# LCCAtmegaXXM1.net
KiCad netlist of a schematic drawn in Altium Designer
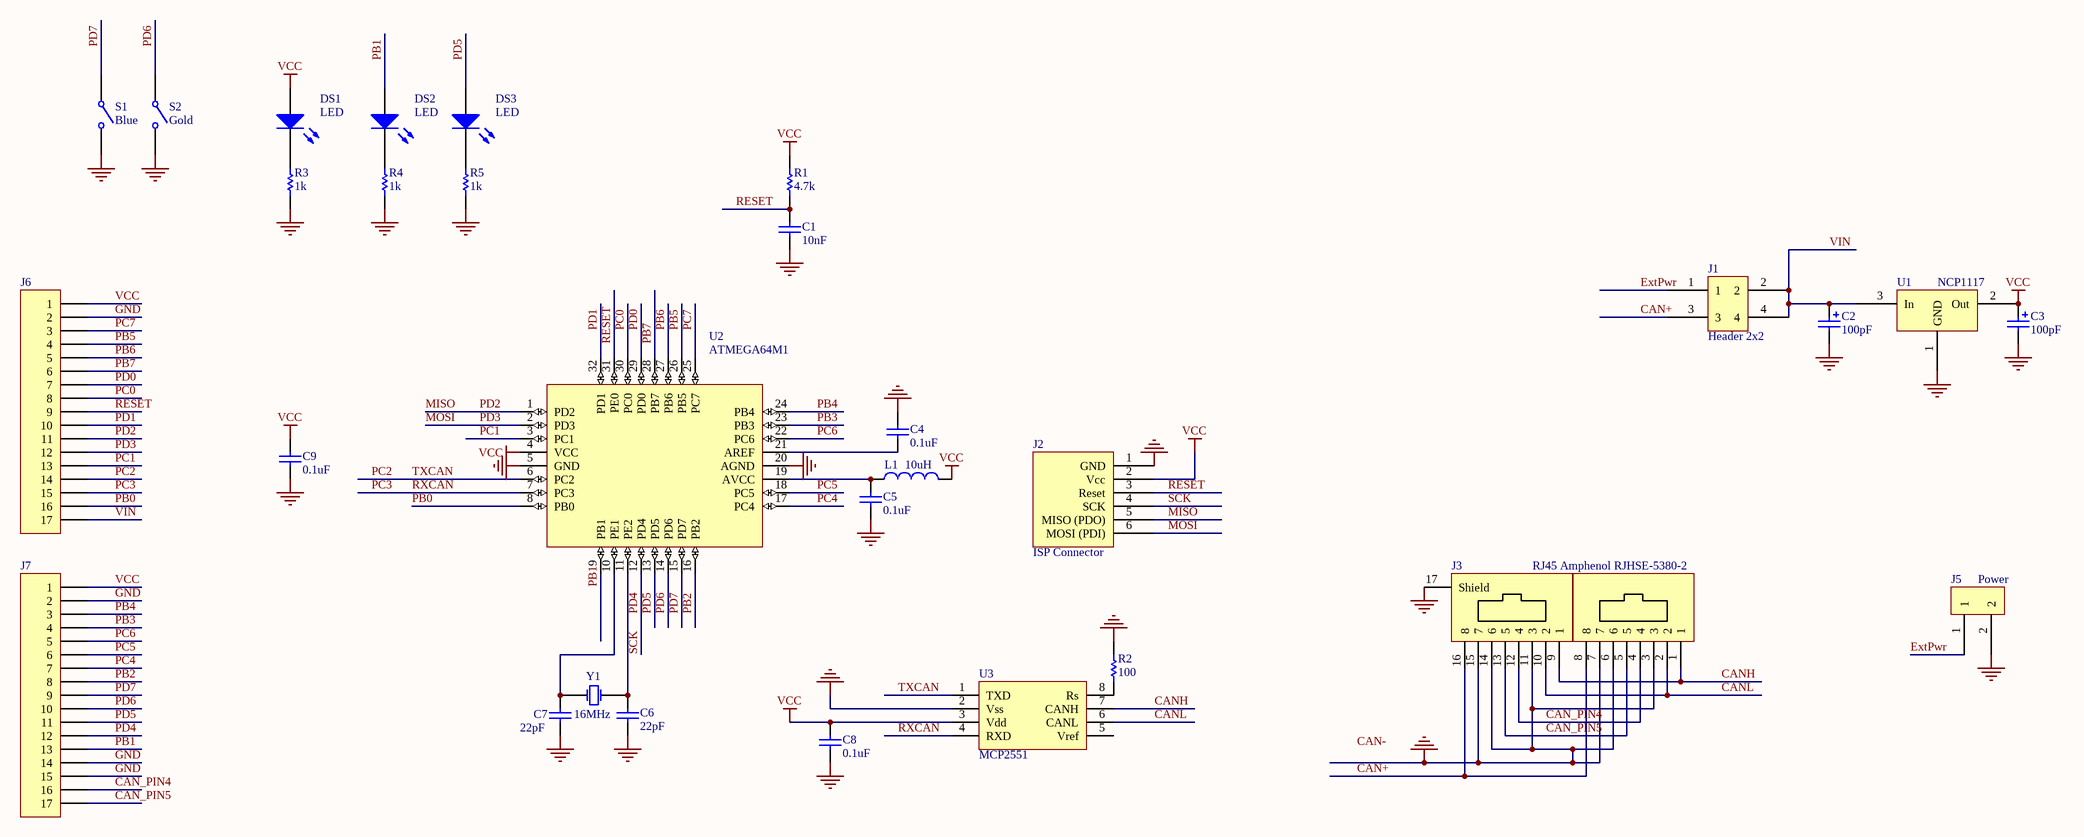
[diagram p0: LCCAtmegaXXM1.SchDoc]

(export (version "E")
  (design (tool "Eeschema 10.0.6"))
  (components
    (comp (ref "C1")
      (value "10nF")
      (footprint "Cap SMD 0805A")
      (description "Capacitor")
      (fields (field (name "Comment") "Cap") (field (name "PUBLISHER") "Altium Limited"))
      (libsource (lib "Custom") (part "Cap"))
    )
    (comp (ref "C2")
      (value "100pF")
      (footprint "Cap SMD Elect 5x5.3")
      (description "Polarized Capacitor (Radial)")
      (fields (field (name "Comment") "Cap Pol") (field (name "PUBLISHER") "Altium Limited"))
      (libsource (lib "Custom") (part "Cap Pol"))
    )
    (comp (ref "C3")
      (value "100pF")
      (footprint "Cap SMD Elect 5x5.3")
      (description "Polarized Capacitor (Radial)")
      (fields (field (name "Comment") "Cap Pol") (field (name "PUBLISHER") "Altium Limited"))
      (libsource (lib "Custom") (part "Cap Pol"))
    )
    (comp (ref "C4")
      (value "0.1uF")
      (footprint "Cap SMD 0805A")
      (description "Capacitor")
      (fields (field (name "Comment") "Cap") (field (name "PUBLISHER") "Altium Limited"))
      (libsource (lib "Custom") (part "Cap"))
    )
    (comp (ref "C5")
      (value "0.1uF")
      (footprint "Cap SMD 0805A")
      (description "Capacitor")
      (fields (field (name "Comment") "Cap") (field (name "PUBLISHER") "Altium Limited"))
      (libsource (lib "Custom") (part "Cap"))
    )
    (comp (ref "C6")
      (value "22pF")
      (footprint "Cap SMD 0805A")
      (description "Capacitor")
      (fields (field (name "Comment") "Cap") (field (name "PUBLISHER") "Altium Limited"))
      (libsource (lib "Custom") (part "Cap"))
    )
    (comp (ref "C7")
      (value "22pF")
      (footprint "Cap SMD 0805A")
      (description "Capacitor")
      (fields (field (name "Comment") "Cap") (field (name "PUBLISHER") "Altium Limited"))
      (libsource (lib "Custom") (part "Cap"))
    )
    (comp (ref "C8")
      (value "0.1uF")
      (footprint "Cap SMD 0805A")
      (description "Capacitor")
      (fields (field (name "Comment") "Cap") (field (name "PUBLISHER") "Altium Limited"))
      (libsource (lib "Custom") (part "Cap"))
    )
    (comp (ref "C9")
      (value "0.1uF")
      (footprint "Cap SMD 0805A")
      (description "Capacitor")
      (fields (field (name "Comment") "Cap") (field (name "PUBLISHER") "Altium Limited"))
      (libsource (lib "Custom") (part "Cap"))
    )
    (comp (ref "DS1")
      (value "LED")
      (footprint "LED SMD 0805")
      (description "RGB LED Common Anode")
      (fields (field (name "PUBLISHER") "Altium Limited"))
      (libsource (lib "Custom") (part "LED"))
    )
    (comp (ref "DS2")
      (value "LED")
      (footprint "LED SMD 0805")
      (description "RGB LED Common Anode")
      (fields (field (name "PUBLISHER") "Altium Limited"))
      (libsource (lib "Custom") (part "LED"))
    )
    (comp (ref "DS3")
      (value "LED")
      (footprint "LED SMD 0805")
      (description "RGB LED Common Anode")
      (fields (field (name "PUBLISHER") "Altium Limited"))
      (libsource (lib "Custom") (part "LED"))
    )
    (comp (ref "J1") (value "Header 2x2") (footprint "HDR2x2") (libsource (lib "Custom") (part "HDR2x2")))
    (comp (ref "J2")
      (value "ISP Connector")
      (footprint "PcbLib1:HDR2x3")
      (libsource (lib "Custom") (part "ISP Connector"))
    )
    (comp (ref "J3")
      (value "RJ45 Amphenol RJHSE-5380-2")
      (footprint "Amphenol RJHSE-5380-2")
      (libsource (lib "Custom") (part "RJ45-2"))
    )
    (comp (ref "J5")
      (value "Power")
      (footprint "DC 2.5mm PCB Jack")
      (libsource (lib "Custom") (part "SIP2 CONNECTOR"))
    )
    (comp (ref "J6")
      (value "Header 17")
      (footprint "HDR1X17")
      (description "Header, 17-Pin")
      (fields (field (name "PUBLISHER") "Altium Limited"))
      (libsource (lib "Miscellaneous Connectors") (part "Header 17"))
    )
    (comp (ref "J7")
      (value "Header 17")
      (footprint "HDR1X17")
      (description "Header, 17-Pin")
      (fields (field (name "PUBLISHER") "Altium Limited"))
      (libsource (lib "Miscellaneous Connectors") (part "Header 17"))
    )
    (comp (ref "L1")
      (value "10uH")
      (footprint "Cap SMD 0805A")
      (description "Inductor")
      (fields (field (name "PUBLISHER") "Altium Limited"))
      (libsource (lib "Miscellaneous Devices") (part "Inductor"))
    )
    (comp (ref "R1")
      (value "4.7k")
      (footprint "Res SMD 0805A")
      (fields (field (name "Comment") "Res1"))
      (libsource (lib "Custom") (part "Resistor"))
    )
    (comp (ref "R2")
      (value "100")
      (footprint "Res SMD 0805A")
      (fields (field (name "Comment") "Res1"))
      (libsource (lib "Custom") (part "Resistor"))
    )
    (comp (ref "R3")
      (value "1k")
      (footprint "Res SMD 0805A")
      (fields (field (name "Comment") "Res1"))
      (libsource (lib "Custom") (part "Resistor"))
    )
    (comp (ref "R4")
      (value "1k")
      (footprint "Res SMD 0805A")
      (fields (field (name "Comment") "Res1"))
      (libsource (lib "Custom") (part "Resistor"))
    )
    (comp (ref "R5")
      (value "1k")
      (footprint "Res SMD 0805A")
      (fields (field (name "Comment") "Res1"))
      (libsource (lib "Custom") (part "Resistor"))
    )
    (comp (ref "S1")
      (value "Blue")
      (footprint "SPST Tactile 6x3.5")
      (description "Push Button, Single-Pole, Single-Throw")
      (fields (field (name "PUBLISHER") "Altium Limited"))
      (libsource (lib "Custom") (part "SW-PB-SPST"))
    )
    (comp (ref "S2")
      (value "Gold")
      (footprint "SPST Tactile 6x3.5")
      (description "Push Button, Single-Pole, Single-Throw")
      (fields (field (name "PUBLISHER") "Altium Limited"))
      (libsource (lib "Custom") (part "SW-PB-SPST"))
    )
    (comp (ref "U1")
      (value "NCP1117")
      (footprint "SOT-223")
      (description "LDO Regulator")
      (libsource (lib "Custom") (part "NCP1117"))
    )
    (comp (ref "U2")
      (value "ATMEGA64M1")
      (footprint "TQFP32")
      (description "8-Bit AVR Microcontroller")
      (fields (field (name "PUBLISHER") "Altium Limited"))
      (libsource (lib "Custom") (part "ATMEGA64M1"))
    )
    (comp (ref "U3")
      (value "MCP2551")
      (footprint "SOIC8")
      (description "MCP2551 High Speed CAN Transceiver")
      (libsource (lib "Custom") (part "MCP2551"))
    )
    (comp (ref "Y1")
      (value "16MHz")
      (footprint "Crystal TXC SMD")
      (description "Crystal Oscillator")
      (fields (field (name "PUBLISHER") "Altium Limited"))
      (libsource (lib "Miscellaneous Devices") (part "XTAL"))
    )
  )
  (nets
    (net (code "1") (name "/CAN+") (class "Default")
      (node (ref "J1") (pin "3") (pinfunction "3_3") (pintype "passive"))
      (node (ref "J3") (pin "16") (pinfunction "8_16") (pintype "passive"))
      (node (ref "J3") (pin "8") (pinfunction "8_8") (pintype "passive"))
    )
    (net (code "3") (name "/CANH") (class "Default")
      (node (ref "J3") (pin "1") (pinfunction "1_1") (pintype "passive"))
      (node (ref "J3") (pin "9") (pinfunction "1_9") (pintype "passive"))
      (node (ref "U3") (pin "7") (pinfunction "CANH_7") (pintype "passive"))
    )
    (net (code "4") (name "/CANL") (class "Default")
      (node (ref "J3") (pin "10") (pinfunction "2_10") (pintype "passive"))
      (node (ref "J3") (pin "2") (pinfunction "2_2") (pintype "passive"))
      (node (ref "U3") (pin "6") (pinfunction "CANL_6") (pintype "passive"))
    )
    (net (code "5") (name "/CAN_PIN4") (class "Default")
      (node (ref "J3") (pin "12") (pinfunction "4_12") (pintype "passive"))
      (node (ref "J3") (pin "4") (pinfunction "4_4") (pintype "passive"))
      (node (ref "J7") (pin "16") (pinfunction "16_16") (pintype "passive"))
    )
    (net (code "6") (name "/CAN_PIN5") (class "Default")
      (node (ref "J3") (pin "13") (pinfunction "5_13") (pintype "passive"))
      (node (ref "J3") (pin "5") (pinfunction "5_5") (pintype "passive"))
      (node (ref "J7") (pin "17") (pinfunction "17_17") (pintype "passive"))
    )
    (net (code "7") (name "/ExtPwr") (class "Default")
      (node (ref "J1") (pin "1") (pinfunction "1_1") (pintype "passive"))
      (node (ref "J5") (pin "1") (pinfunction "1_1") (pintype "passive"))
    )
    (net (code "8") (name "/MISO") (class "Default")
      (node (ref "J2") (pin "5") (pinfunction "MISO_(PDO)_5") (pintype "passive"))
      (node (ref "J6") (pin "11") (pinfunction "11_11") (pintype "passive"))
      (node (ref "U2") (pin "1") (pinfunction "PD2_1") (pintype "bidirectional"))
    )
    (net (code "9") (name "/MOSI") (class "Default")
      (node (ref "J2") (pin "6") (pinfunction "MOSI_(PDI)_6") (pintype "passive"))
      (node (ref "J6") (pin "12") (pinfunction "12_12") (pintype "passive"))
      (node (ref "U2") (pin "2") (pinfunction "PD3_2") (pintype "bidirectional"))
    )
    (net (code "10") (name "/PB0") (class "Default")
      (node (ref "J6") (pin "16") (pinfunction "16_16") (pintype "passive"))
      (node (ref "U2") (pin "8") (pinfunction "PB0_8") (pintype "bidirectional"))
    )
    (net (code "11") (name "/PB1") (class "Default")
      (node (ref "DS2") (pin "A") (pinfunction "A_A") (pintype "passive"))
      (node (ref "J7") (pin "13") (pinfunction "13_13") (pintype "passive"))
      (node (ref "U2") (pin "9") (pinfunction "PB1_9") (pintype "bidirectional"))
    )
    (net (code "12") (name "/PB2") (class "Default")
      (node (ref "J7") (pin "8") (pinfunction "8_8") (pintype "passive"))
      (node (ref "U2") (pin "16") (pinfunction "PB2_16") (pintype "bidirectional"))
    )
    (net (code "13") (name "/PB3") (class "Default")
      (node (ref "J7") (pin "4") (pinfunction "4_4") (pintype "passive"))
      (node (ref "U2") (pin "23") (pinfunction "PB3_23") (pintype "bidirectional"))
    )
    (net (code "14") (name "/PB4") (class "Default")
      (node (ref "J7") (pin "3") (pinfunction "3_3") (pintype "passive"))
      (node (ref "U2") (pin "24") (pinfunction "PB4_24") (pintype "bidirectional"))
    )
    (net (code "15") (name "/PB5") (class "Default")
      (node (ref "J6") (pin "4") (pinfunction "4_4") (pintype "passive"))
      (node (ref "U2") (pin "26") (pinfunction "PB5_26") (pintype "bidirectional"))
    )
    (net (code "16") (name "/PB6") (class "Default")
      (node (ref "J6") (pin "5") (pinfunction "5_5") (pintype "passive"))
      (node (ref "U2") (pin "27") (pinfunction "PB6_27") (pintype "bidirectional"))
    )
    (net (code "17") (name "/PB7") (class "Default")
      (node (ref "J6") (pin "6") (pinfunction "6_6") (pintype "passive"))
      (node (ref "U2") (pin "28") (pinfunction "PB7_28") (pintype "bidirectional"))
    )
    (net (code "18") (name "/PC0") (class "Default")
      (node (ref "J6") (pin "8") (pinfunction "8_8") (pintype "passive"))
      (node (ref "U2") (pin "30") (pinfunction "PC0_30") (pintype "bidirectional"))
    )
    (net (code "19") (name "/PC1") (class "Default")
      (node (ref "J6") (pin "13") (pinfunction "13_13") (pintype "passive"))
      (node (ref "U2") (pin "3") (pinfunction "PC1_3") (pintype "bidirectional"))
    )
    (net (code "20") (name "/PC2") (class "Default")
      (node (ref "J6") (pin "14") (pinfunction "14_14") (pintype "passive"))
      (node (ref "U2") (pin "6") (pinfunction "PC2_6") (pintype "bidirectional"))
      (node (ref "U3") (pin "1") (pinfunction "TXD_1") (pintype "passive"))
    )
    (net (code "21") (name "/PC3") (class "Default")
      (node (ref "J6") (pin "15") (pinfunction "15_15") (pintype "passive"))
      (node (ref "U2") (pin "7") (pinfunction "PC3_7") (pintype "bidirectional"))
      (node (ref "U3") (pin "4") (pinfunction "RXD_4") (pintype "passive"))
    )
    (net (code "22") (name "/PC4") (class "Default")
      (node (ref "J7") (pin "7") (pinfunction "7_7") (pintype "passive"))
      (node (ref "U2") (pin "17") (pinfunction "PC4_17") (pintype "bidirectional"))
    )
    (net (code "23") (name "/PC5") (class "Default")
      (node (ref "J7") (pin "6") (pinfunction "6_6") (pintype "passive"))
      (node (ref "U2") (pin "18") (pinfunction "PC5_18") (pintype "bidirectional"))
    )
    (net (code "24") (name "/PC6") (class "Default")
      (node (ref "J7") (pin "5") (pinfunction "5_5") (pintype "passive"))
      (node (ref "U2") (pin "22") (pinfunction "PC6_22") (pintype "bidirectional"))
    )
    (net (code "25") (name "/PC7") (class "Default")
      (node (ref "J6") (pin "3") (pinfunction "3_3") (pintype "passive"))
      (node (ref "U2") (pin "25") (pinfunction "PC7_25") (pintype "bidirectional"))
    )
    (net (code "26") (name "/PD0") (class "Default")
      (node (ref "J6") (pin "7") (pinfunction "7_7") (pintype "passive"))
      (node (ref "U2") (pin "29") (pinfunction "PD0_29") (pintype "bidirectional"))
    )
    (net (code "27") (name "/PD1") (class "Default")
      (node (ref "J6") (pin "10") (pinfunction "10_10") (pintype "passive"))
      (node (ref "U2") (pin "32") (pinfunction "PD1_32") (pintype "bidirectional"))
    )
    (net (code "28") (name "/PD4") (class "Default")
      (node (ref "J2") (pin "4") (pinfunction "SCK_4") (pintype "passive"))
      (node (ref "J7") (pin "12") (pinfunction "12_12") (pintype "passive"))
      (node (ref "U2") (pin "12") (pinfunction "PD4_12") (pintype "bidirectional"))
    )
    (net (code "29") (name "/PD5") (class "Default")
      (node (ref "DS3") (pin "A") (pinfunction "A_A") (pintype "passive"))
      (node (ref "J7") (pin "11") (pinfunction "11_11") (pintype "passive"))
      (node (ref "U2") (pin "13") (pinfunction "PD5_13") (pintype "bidirectional"))
    )
    (net (code "30") (name "/PD6") (class "Default")
      (node (ref "J7") (pin "10") (pinfunction "10_10") (pintype "passive"))
      (node (ref "S2") (pin "1") (pinfunction "1_1") (pintype "passive"))
      (node (ref "U2") (pin "14") (pinfunction "PD6_14") (pintype "bidirectional"))
    )
    (net (code "31") (name "/PD7") (class "Default")
      (node (ref "J7") (pin "9") (pinfunction "9_9") (pintype "passive"))
      (node (ref "S1") (pin "1") (pinfunction "1_1") (pintype "passive"))
      (node (ref "U2") (pin "15") (pinfunction "PD7_15") (pintype "bidirectional"))
    )
    (net (code "32") (name "/RESET") (class "Default")
      (node (ref "C1") (pin "1") (pinfunction "1_1") (pintype "passive"))
      (node (ref "J2") (pin "3") (pinfunction "Reset_3") (pintype "passive"))
      (node (ref "J6") (pin "9") (pinfunction "9_9") (pintype "passive"))
      (node (ref "R1") (pin "1") (pinfunction "1_1") (pintype "passive"))
      (node (ref "U2") (pin "31") (pinfunction "PE0_31") (pintype "bidirectional"))
    )
    (net (code "33") (name "/VIN") (class "Default")
      (node (ref "C2") (pin "1") (pinfunction "1_1") (pintype "passive"))
      (node (ref "J1") (pin "2") (pinfunction "2_2") (pintype "passive"))
      (node (ref "J1") (pin "4") (pinfunction "4_4") (pintype "passive"))
      (node (ref "J6") (pin "17") (pinfunction "17_17") (pintype "passive"))
      (node (ref "U1") (pin "3") (pinfunction "In_3") (pintype "passive"))
    )
    (net (code "34") (name "GND") (class "Default")
      (node (ref "C1") (pin "2") (pinfunction "2_2") (pintype "passive"))
      (node (ref "C2") (pin "2") (pinfunction "2_2") (pintype "passive"))
      (node (ref "C3") (pin "2") (pinfunction "2_2") (pintype "passive"))
      (node (ref "C4") (pin "2") (pinfunction "2_2") (pintype "passive"))
      (node (ref "C5") (pin "2") (pinfunction "2_2") (pintype "passive"))
      (node (ref "C6") (pin "1") (pinfunction "1_1") (pintype "passive"))
      (node (ref "C7") (pin "1") (pinfunction "1_1") (pintype "passive"))
      (node (ref "C8") (pin "2") (pinfunction "2_2") (pintype "passive"))
      (node (ref "C9") (pin "2") (pinfunction "2_2") (pintype "passive"))
      (node (ref "J2") (pin "1") (pinfunction "GND_1") (pintype "passive"))
      (node (ref "J3") (pin "11") (pinfunction "3_11") (pintype "passive"))
      (node (ref "J3") (pin "14") (pinfunction "6_14") (pintype "passive"))
      (node (ref "J3") (pin "15") (pinfunction "7_15") (pintype "passive"))
      (node (ref "J3") (pin "17") (pinfunction "Shield_17") (pintype "passive"))
      (node (ref "J3") (pin "3") (pinfunction "3_3") (pintype "passive"))
      (node (ref "J3") (pin "6") (pinfunction "6_6") (pintype "passive"))
      (node (ref "J3") (pin "7") (pinfunction "7_7") (pintype "passive"))
      (node (ref "J5") (pin "2") (pinfunction "2_2") (pintype "passive"))
      (node (ref "J6") (pin "2") (pinfunction "2_2") (pintype "passive"))
      (node (ref "J7") (pin "14") (pinfunction "14_14") (pintype "passive"))
      (node (ref "J7") (pin "15") (pinfunction "15_15") (pintype "passive"))
      (node (ref "J7") (pin "2") (pinfunction "2_2") (pintype "passive"))
      (node (ref "R2") (pin "1") (pinfunction "1_1") (pintype "passive"))
      (node (ref "R3") (pin "1") (pinfunction "1_1") (pintype "passive"))
      (node (ref "R4") (pin "1") (pinfunction "1_1") (pintype "passive"))
      (node (ref "R5") (pin "1") (pinfunction "1_1") (pintype "passive"))
      (node (ref "S1") (pin "2") (pinfunction "2_2") (pintype "passive"))
      (node (ref "S2") (pin "2") (pinfunction "2_2") (pintype "passive"))
      (node (ref "U1") (pin "1") (pinfunction "GND_1") (pintype "passive"))
      (node (ref "U2") (pin "20") (pinfunction "AGND_20") (pintype "power_in"))
      (node (ref "U2") (pin "5") (pinfunction "GND_5") (pintype "power_in"))
      (node (ref "U3") (pin "2") (pinfunction "Vss_2") (pintype "passive"))
    )
    (net (code "35") (name "Net-(DS1-PadK)") (class "Default")
      (node (ref "DS1") (pin "K") (pinfunction "K_K") (pintype "passive"))
      (node (ref "R3") (pin "2") (pinfunction "2_2") (pintype "passive"))
    )
    (net (code "36") (name "Net-(DS2-PadK)") (class "Default")
      (node (ref "DS2") (pin "K") (pinfunction "K_K") (pintype "passive"))
      (node (ref "R4") (pin "2") (pinfunction "2_2") (pintype "passive"))
    )
    (net (code "37") (name "Net-(DS3-PadK)") (class "Default")
      (node (ref "DS3") (pin "K") (pinfunction "K_K") (pintype "passive"))
      (node (ref "R5") (pin "2") (pinfunction "2_2") (pintype "passive"))
    )
    (net (code "38") (name "Net-(U2-AREF)") (class "Default")
      (node (ref "C4") (pin "1") (pinfunction "1_1") (pintype "passive"))
      (node (ref "U2") (pin "21") (pinfunction "AREF_21") (pintype "passive"))
    )
    (net (code "39") (name "Net-(U2-AVCC)") (class "Default")
      (node (ref "C5") (pin "1") (pinfunction "1_1") (pintype "passive"))
      (node (ref "L1") (pin "1") (pinfunction "1_1") (pintype "passive"))
      (node (ref "U2") (pin "19") (pinfunction "AVCC_19") (pintype "power_in"))
    )
    (net (code "40") (name "Net-(U2-PE1)") (class "Default")
      (node (ref "C7") (pin "2") (pinfunction "2_2") (pintype "passive"))
      (node (ref "U2") (pin "10") (pinfunction "PE1_10") (pintype "bidirectional"))
      (node (ref "Y1") (pin "1") (pinfunction "OSC1_1") (pintype "passive"))
    )
    (net (code "41") (name "Net-(U2-PE2)") (class "Default")
      (node (ref "C6") (pin "2") (pinfunction "2_2") (pintype "passive"))
      (node (ref "U2") (pin "11") (pinfunction "PE2_11") (pintype "bidirectional"))
      (node (ref "Y1") (pin "2") (pinfunction "OSC2_2") (pintype "passive"))
    )
    (net (code "42") (name "Net-(U3-Rs)") (class "Default")
      (node (ref "R2") (pin "2") (pinfunction "2_2") (pintype "passive"))
      (node (ref "U3") (pin "8") (pinfunction "Rs_8") (pintype "passive"))
    )
    (net (code "43") (name "VCC") (class "Default")
      (node (ref "C3") (pin "1") (pinfunction "1_1") (pintype "passive"))
      (node (ref "C8") (pin "1") (pinfunction "1_1") (pintype "passive"))
      (node (ref "C9") (pin "1") (pinfunction "1_1") (pintype "passive"))
      (node (ref "DS1") (pin "A") (pinfunction "A_A") (pintype "passive"))
      (node (ref "J2") (pin "2") (pinfunction "Vcc_2") (pintype "passive"))
      (node (ref "J6") (pin "1") (pinfunction "1_1") (pintype "passive"))
      (node (ref "J7") (pin "1") (pinfunction "1_1") (pintype "passive"))
      (node (ref "L1") (pin "2") (pinfunction "2_2") (pintype "passive"))
      (node (ref "R1") (pin "2") (pinfunction "2_2") (pintype "passive"))
      (node (ref "U1") (pin "2") (pinfunction "Out_2") (pintype "passive"))
      (node (ref "U2") (pin "4") (pinfunction "VCC_4") (pintype "power_in"))
      (node (ref "U3") (pin "3") (pinfunction "Vdd_3") (pintype "passive"))
    )
    (net (code "44") (name "unconnected-(U3-Vref-Pad5)") (class "Default")
      (node (ref "U3") (pin "5") (pinfunction "Vref_5") (pintype "passive"))
    )
  )
)
